# Wheelspeed_rev11.net
KiCad netlist of a schematic drawn in EAGLE
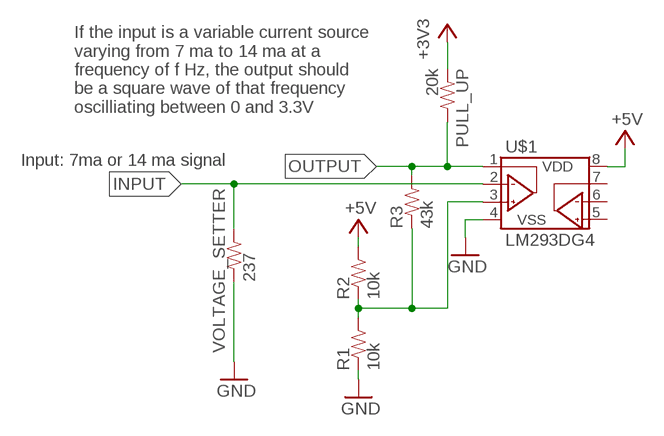
[diagram p0: schematic, sheet 1]

(export (version "E")
  (design (tool "Eeschema 10.0.6"))
  (components
    (comp (ref "PULL_UP")
      (value "20k")
      (footprint "eagle-import:0603-RES")
      (libsource (lib "eagle-import") (part "RESISTOR0603"))
    )
    (comp (ref "R1")
      (value "10k")
      (footprint "eagle-import:0603-RES")
      (libsource (lib "eagle-import") (part "RESISTOR0603"))
    )
    (comp (ref "R2")
      (value "10k")
      (footprint "eagle-import:0603-RES")
      (libsource (lib "eagle-import") (part "RESISTOR0603"))
    )
    (comp (ref "R3")
      (value "43k")
      (footprint "eagle-import:0603-RES")
      (libsource (lib "eagle-import") (part "RESISTOR0603"))
    )
    (comp (ref "U$1")
      (value "LM293DG4")
      (footprint "eagle-import:SOIC-08")
      (libsource (lib "eagle-import") (part "LM293DG4"))
    )
    (comp (ref "VOLTAGE_SETTER")
      (value "237")
      (footprint "eagle-import:0603-RES")
      (libsource (lib "eagle-import") (part "RESISTOR0603"))
    )
  )
  (nets
    (net (code "1") (name "+3V3") (class "Default")
      (node (ref "PULL_UP") (pin "1") (pinfunction "1_1") (pintype "passive"))
    )
    (net (code "2") (name "+5V") (class "Default")
      (node (ref "R2") (pin "2") (pinfunction "2_2") (pintype "passive"))
      (node (ref "U$1") (pin "8") (pinfunction "VDD_8") (pintype "passive"))
    )
    (net (code "3") (name "GND") (class "Default")
      (node (ref "R1") (pin "1") (pinfunction "1_1") (pintype "passive"))
      (node (ref "U$1") (pin "4") (pinfunction "VSS_4") (pintype "passive"))
      (node (ref "VOLTAGE_SETTER") (pin "1") (pinfunction "1_1") (pintype "passive"))
    )
    (net (code "4") (name "INPUT") (class "Default")
      (node (ref "U$1") (pin "2") (pinfunction "VINA-_2") (pintype "passive"))
      (node (ref "VOLTAGE_SETTER") (pin "2") (pinfunction "2_2") (pintype "passive"))
    )
    (net (code "5") (name "Net-(U$1-VINA+)") (class "Default")
      (node (ref "R1") (pin "2") (pinfunction "2_2") (pintype "passive"))
      (node (ref "R2") (pin "1") (pinfunction "1_1") (pintype "passive"))
      (node (ref "R3") (pin "1") (pinfunction "1_1") (pintype "passive"))
      (node (ref "U$1") (pin "3") (pinfunction "VINA+_3") (pintype "passive"))
    )
    (net (code "6") (name "OUTPUT") (class "Default")
      (node (ref "PULL_UP") (pin "2") (pinfunction "2_2") (pintype "passive"))
      (node (ref "R3") (pin "2") (pinfunction "2_2") (pintype "passive"))
      (node (ref "U$1") (pin "1") (pinfunction "VOUTA_1") (pintype "passive"))
    )
    (net (code "7") (name "unconnected-(U$1-VINB+-Pad5)") (class "Default")
      (node (ref "U$1") (pin "5") (pinfunction "VINB+_5") (pintype "passive"))
    )
    (net (code "8") (name "unconnected-(U$1-VINB--Pad6)") (class "Default")
      (node (ref "U$1") (pin "6") (pinfunction "VINB-_6") (pintype "passive"))
    )
    (net (code "9") (name "unconnected-(U$1-VOUTB-Pad7)") (class "Default")
      (node (ref "U$1") (pin "7") (pinfunction "VOUTB_7") (pintype "passive"))
    )
  )
)
